# 07_POWER-RAILS.net
KiCad netlist of a schematic drawn in Altium Designer
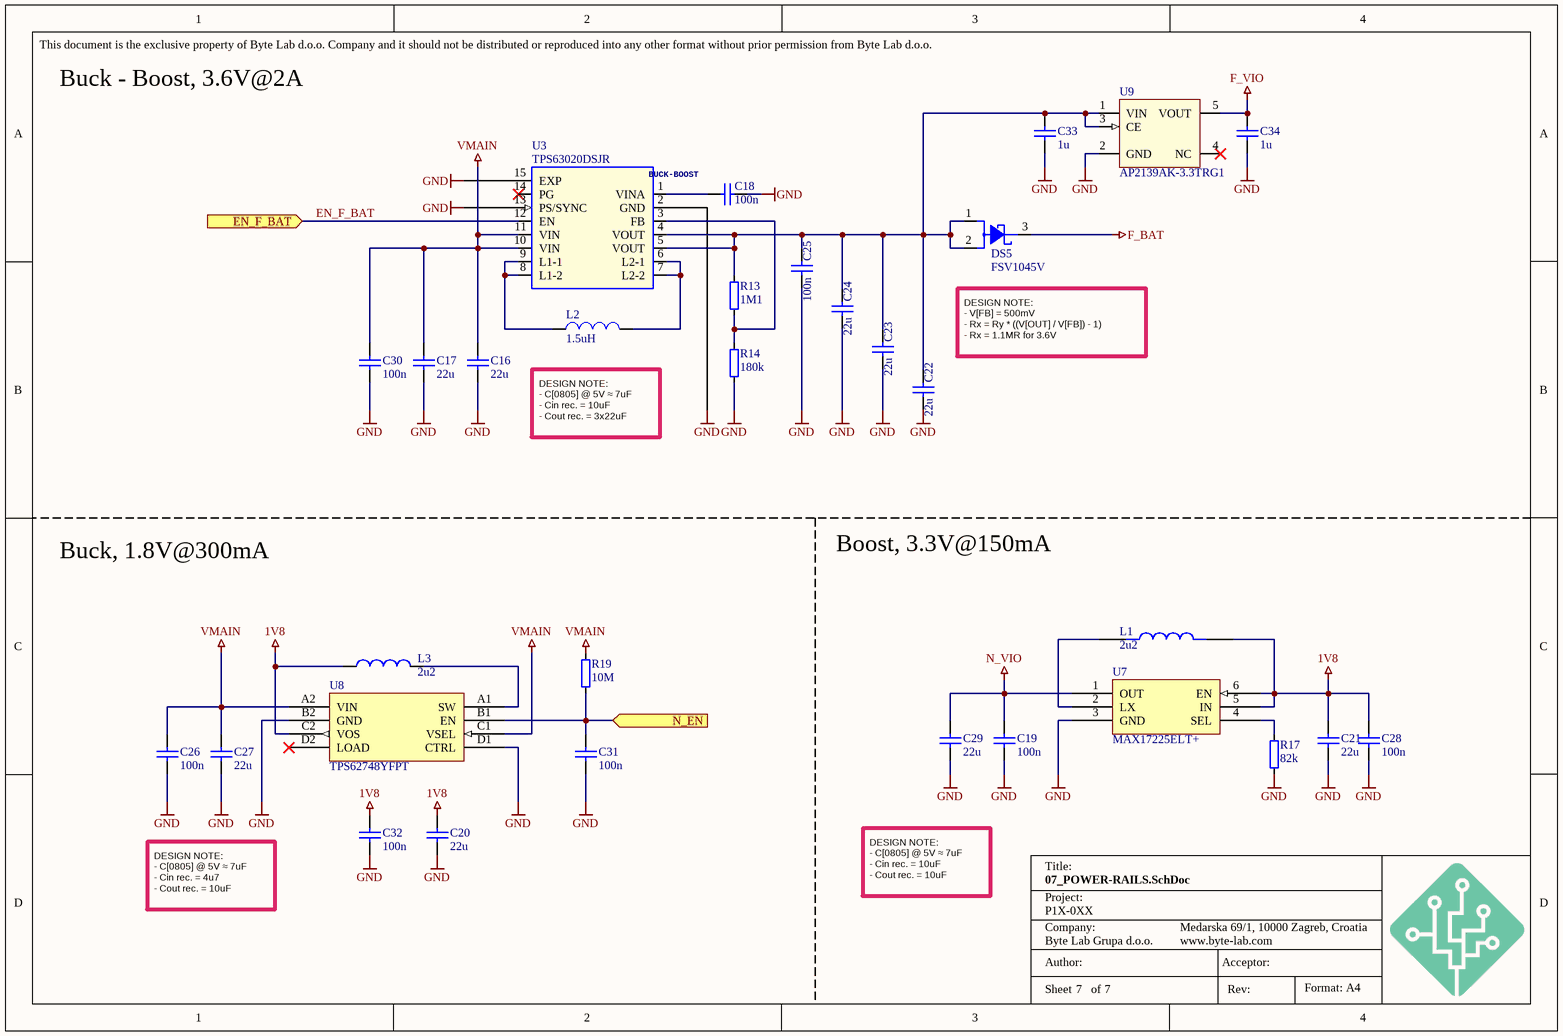
[diagram p0: 07_POWER-RAILS.SchDoc]

(export (version "E")
  (design (tool "Eeschema 10.0.6"))
  (components
    (comp (ref "C16")
      (value "22u")
      (footprint "C-0805")
      (description "Capacitor ceramic 22u ±10% X5R 16V 0805")
      (fields
        (field (name "BL PART NUMBER") "2006-222")
        (field (name "DRAWN_BY") "Fumic")
        (field (name "CHECKED_BY") "Hamin")
      )
      (libsource (lib "BL_Passive") (part "C0805-22u-16V-X5R"))
    )
    (comp (ref "C17")
      (value "22u")
      (footprint "C-0805")
      (description "Capacitor ceramic 22u ±10% X5R 16V 0805")
      (fields
        (field (name "BL PART NUMBER") "2006-222")
        (field (name "DRAWN_BY") "Fumic")
        (field (name "CHECKED_BY") "Hamin")
      )
      (libsource (lib "BL_Passive") (part "C0805-22u-16V-X5R"))
    )
    (comp (ref "C18")
      (value "100n")
      (footprint "C-0402")
      (description "Capacitor ceramic 100n ±10% X7R 16V 0402")
      (fields
        (field (name "BL PART NUMBER") "2000-908")
        (field (name "DRAWN_BY") "Puskar")
        (field (name "CHECKED_BY") "Dodig")
      )
      (libsource (lib "BL_Passive") (part "C0402-100n-16V-X7R"))
    )
    (comp (ref "C19")
      (value "100n")
      (footprint "C-0402")
      (description "Capacitor ceramic 100n ±10% X7R 16V 0402")
      (fields
        (field (name "BL PART NUMBER") "2000-908")
        (field (name "DRAWN_BY") "Puskar")
        (field (name "CHECKED_BY") "Dodig")
      )
      (libsource (lib "BL_Passive") (part "C0402-100n-16V-X7R"))
    )
    (comp (ref "C20")
      (value "22u")
      (footprint "C-0805")
      (description "Capacitor ceramic 22u ±10% X5R 16V 0805")
      (fields
        (field (name "BL PART NUMBER") "2006-222")
        (field (name "DRAWN_BY") "Fumic")
        (field (name "CHECKED_BY") "Hamin")
      )
      (libsource (lib "BL_Passive") (part "C0805-22u-16V-X5R"))
    )
    (comp (ref "C21")
      (value "22u")
      (footprint "C-0805")
      (description "Capacitor ceramic 22u ±10% X5R 16V 0805")
      (fields
        (field (name "BL PART NUMBER") "2006-222")
        (field (name "DRAWN_BY") "Fumic")
        (field (name "CHECKED_BY") "Hamin")
      )
      (libsource (lib "BL_Passive") (part "C0805-22u-16V-X5R"))
    )
    (comp (ref "C22")
      (value "22u")
      (footprint "C-0805")
      (description "Capacitor ceramic 22u ±10% X5R 16V 0805")
      (fields
        (field (name "BL PART NUMBER") "2006-222")
        (field (name "DRAWN_BY") "Fumic")
        (field (name "CHECKED_BY") "Hamin")
      )
      (libsource (lib "BL_Passive") (part "C0805-22u-16V-X5R"))
    )
    (comp (ref "C23")
      (value "22u")
      (footprint "C-0805")
      (description "Capacitor ceramic 22u ±10% X5R 16V 0805")
      (fields
        (field (name "BL PART NUMBER") "2006-222")
        (field (name "DRAWN_BY") "Fumic")
        (field (name "CHECKED_BY") "Hamin")
      )
      (libsource (lib "BL_Passive") (part "C0805-22u-16V-X5R"))
    )
    (comp (ref "C24")
      (value "22u")
      (footprint "C-0805")
      (description "Capacitor ceramic 22u ±10% X5R 16V 0805")
      (fields
        (field (name "BL PART NUMBER") "2006-222")
        (field (name "DRAWN_BY") "Fumic")
        (field (name "CHECKED_BY") "Hamin")
      )
      (libsource (lib "BL_Passive") (part "C0805-22u-16V-X5R"))
    )
    (comp (ref "C25")
      (value "100n")
      (footprint "C-0402")
      (description "Capacitor ceramic 100n ±10% X7R 16V 0402")
      (fields
        (field (name "BL PART NUMBER") "2000-908")
        (field (name "DRAWN_BY") "Puskar")
        (field (name "CHECKED_BY") "Dodig")
      )
      (libsource (lib "BL_Passive") (part "C0402-100n-16V-X7R"))
    )
    (comp (ref "C26")
      (value "100n")
      (footprint "C-0402")
      (description "Capacitor ceramic 100n ±10% X7R 16V 0402")
      (fields
        (field (name "BL PART NUMBER") "2000-908")
        (field (name "DRAWN_BY") "Puskar")
        (field (name "CHECKED_BY") "Dodig")
      )
      (libsource (lib "BL_Passive") (part "C0402-100n-16V-X7R"))
    )
    (comp (ref "C27")
      (value "22u")
      (footprint "C-0805")
      (description "Capacitor ceramic 22u ±10% X5R 16V 0805")
      (fields
        (field (name "BL PART NUMBER") "2006-222")
        (field (name "DRAWN_BY") "Fumic")
        (field (name "CHECKED_BY") "Hamin")
      )
      (libsource (lib "BL_Passive") (part "C0805-22u-16V-X5R"))
    )
    (comp (ref "C28")
      (value "100n")
      (footprint "C-0402")
      (description "Capacitor ceramic 100n ±10% X7R 16V 0402")
      (fields
        (field (name "BL PART NUMBER") "2000-908")
        (field (name "DRAWN_BY") "Puskar")
        (field (name "CHECKED_BY") "Dodig")
      )
      (libsource (lib "BL_Passive") (part "C0402-100n-16V-X7R"))
    )
    (comp (ref "C29")
      (value "22u")
      (footprint "C-0805")
      (description "Capacitor ceramic 22u ±10% X5R 16V 0805")
      (fields
        (field (name "BL PART NUMBER") "2006-222")
        (field (name "DRAWN_BY") "Fumic")
        (field (name "CHECKED_BY") "Hamin")
      )
      (libsource (lib "BL_Passive") (part "C0805-22u-16V-X5R"))
    )
    (comp (ref "C30")
      (value "100n")
      (footprint "C-0402")
      (description "Capacitor ceramic 100n ±10% X7R 16V 0402")
      (fields
        (field (name "BL PART NUMBER") "2000-908")
        (field (name "DRAWN_BY") "Puskar")
        (field (name "CHECKED_BY") "Dodig")
      )
      (libsource (lib "BL_Passive") (part "C0402-100n-16V-X7R"))
    )
    (comp (ref "C31")
      (value "100n")
      (footprint "C-0402")
      (description "Capacitor ceramic 100n ±10% X7R 16V 0402")
      (fields
        (field (name "BL PART NUMBER") "2000-908")
        (field (name "DRAWN_BY") "Puskar")
        (field (name "CHECKED_BY") "Dodig")
      )
      (libsource (lib "BL_Passive") (part "C0402-100n-16V-X7R"))
    )
    (comp (ref "C32")
      (value "100n")
      (footprint "C-0402")
      (description "Capacitor ceramic 100n ±10% X7R 16V 0402")
      (fields
        (field (name "BL PART NUMBER") "2000-908")
        (field (name "DRAWN_BY") "Puskar")
        (field (name "CHECKED_BY") "Dodig")
      )
      (libsource (lib "BL_Passive") (part "C0402-100n-16V-X7R"))
    )
    (comp (ref "C33")
      (value "1u")
      (footprint "C-0603")
      (description "Capacitor ceramic 1u ±10% X5R 25V")
      (fields
        (field (name "MANUFACTURER") "Yageo")
        (field (name "BL PART NUMBER") "2006-223")
        (field (name "DRAWN_BY") "Hamin")
        (field (name "CHECKED_BY") "Golubic")
      )
      (libsource (lib "BL_Passive") (part "C0603-1u-25V-X5R"))
    )
    (comp (ref "C34")
      (value "1u")
      (footprint "C-0603")
      (description "Capacitor ceramic 1u ±10% X5R 25V")
      (fields
        (field (name "MANUFACTURER") "Yageo")
        (field (name "BL PART NUMBER") "2006-223")
        (field (name "DRAWN_BY") "Hamin")
        (field (name "CHECKED_BY") "Golubic")
      )
      (libsource (lib "BL_Passive") (part "C0603-1u-25V-X5R"))
    )
    (comp (ref "DS5")
      (value "FSV1045V")
      (footprint "TO277-3")
      (description "DIODO SCHOTTKY 10A 45V FSV1045V TO277-3 SMT")
      (fields
        (field (name "BL PART NUMBER") "2007-712")
        (field (name "MANUFACTURER") "onsemi")
        (field (name "DRAWN_BY") "Blues Wireless")
      )
      (libsource (lib "n21-p2") (part "SCHOTTKY - FSV1045V - 10A/45V"))
    )
    (comp (ref "L1")
      (value "2u2")
      (footprint "IND_XFL4020-222MEC")
      (description "Power Inductors - SMD 2.2Uh Shld 8A 23.5mOhms AECQ2")
      (fields (field (name "BL PART NUMBER") "2007-483") (field (name "DRAWN_BY") "Blues Wireless"))
      (libsource (lib "n21-p2") (part "XFL4020-222MEC"))
    )
    (comp (ref "L2")
      (value "1.5uH")
      (footprint "VCHA042A-1R5MS6")
      (description "Fixed Ind 1.5UH 7.3A 15.4 Mohm")
      (fields
        (field (name "MANUFACTURER") "Cyntec")
        (field (name "MANUFACTURER PART NUMBER") "VCHA042A-1R5MS6")
        (field (name "DRAWN_BY") "Blues Wireless")
      )
      (libsource (lib "n21-p2") (part "VCHA042A-1R5MS6"))
    )
    (comp (ref "L3")
      (value "2u2")
      (footprint "1285AS-H-2R2M=P2-INDC2016X100N")
      (description "FIXED IND 2.2UH 1.5A 204MOHM SMD")
      (fields
        (field (name "MANUFACTURER") "Murata Electronics")
        (field (name "MANUFACTURER PART NUMBER") "1285AS-H-2R2M=P2")
        (field (name "DRAWN_BY") "Blues Wireless")
      )
      (libsource (lib "n21-p2") (part "1285AS-H-2R2M=P2"))
    )
    (comp (ref "R13")
      (value "1M1")
      (footprint "R-0402")
      (description "Resistor 1M1 ±1% 0402")
      (fields
        (field (name "BL PART NUMBER") "2000-730")
        (field (name "CHECKED_BY") "Kvesic")
        (field (name "DRAWN_BY") "Hamin")
      )
      (libsource (lib "BL_Passive") (part "R0402-1M1-1"))
    )
    (comp (ref "R14")
      (value "180k")
      (footprint "R-0402")
      (description "Resistor 180k ±1% 0402")
      (fields
        (field (name "BL PART NUMBER") "2001-422")
        (field (name "CHECKED_BY") "Hamin")
        (field (name "DRAWN_BY") "Dodig")
      )
      (libsource (lib "BL_Passive") (part "R0402-180k-1"))
    )
    (comp (ref "R17")
      (value "82k")
      (footprint "R-0402")
      (description "Resistor 82k ±1% 0402")
      (fields
        (field (name "MANUFACTURER") "Yageo")
        (field (name "MANUFACTURER PART NUMBER") "RC0402FR-0782KL")
        (field (name "CHECKED_BY") "Hamin")
        (field (name "DRAWN_BY") "Puskar")
      )
      (libsource (lib "BL_Passive") (part "R0402-82k-1"))
    )
    (comp (ref "R19")
      (value "10M")
      (footprint "BL_Passive:R-0402")
      (description "Resistor 10M ±1% 0402")
      (fields
        (field (name "BL PART NUMBER") "2002-832")
        (field (name "CHECKED_BY") "Dodig")
        (field (name "DRAWN_BY") "Zvonc")
      )
      (libsource (lib "BL_Passive") (part "R0402-10M-1"))
    )
    (comp (ref "U3")
      (value "TPS63020DSJR")
      (footprint "TI PVSON-14 DSJ")
      (description "I.C. DC/DC CONVERTER TPS63020DSJR TEXAS VSON14 SMT")
      (fields
        (field (name "BL PART NUMBER") "2002-405")
        (field (name "MANUFACTURER") "Texas Instruments")
        (field (name "DRAWN_BY") "Blues Wireless")
      )
      (libsource (lib "n21-p2") (part "BUCK-BOOST - TPS63020DSJR"))
    )
    (comp (ref "U7")
      (value "MAX17225ELT+")
      (footprint "MAX17225ELT+UDFN")
      (description "IC REG BOOST ADJ 1A NANO 6UDFN")
      (fields
        (field (name "MANUFACTURER") "Maxim")
        (field (name "BL PART NUMBER") "2007-481")
        (field (name "DRAWN_BY") "Blues Wireless")
      )
      (libsource (lib "n21-p2") (part "MAX17225ELT+"))
    )
    (comp (ref "U8")
      (value "TPS62748YFPT")
      (footprint "TPS62748YFPT-DSBGA4x2")
      (description "IC REG BUCK PROG 300MA 8DSBGA")
      (fields
        (field (name "MANUFACTURER") "Texas Instruments")
        (field (name "BL PART NUMBER") "2007-480")
        (field (name "DRAWN_BY") "Blues Wireless")
      )
      (libsource (lib "n21-p2") (part "TPS62748YFPT"))
    )
    (comp (ref "U9")
      (value "AP2139AK-3.3TRG1")
      (footprint "BL_Components:SOT-23-5(M5)")
      (description "IC REG LINEAR 3.3V 250MA SOT23-5")
      (fields
        (field (name "MANUFACTURER") "Diodes Incorporated")
        (field (name "BL PART NUMBER") "2006-845")
        (field (name "CHECKED_BY") "Hlupic")
        (field (name "DRAWN_BY") "Marsic")
      )
      (libsource (lib "BL_Analog") (part "AP2139AK-3.3TRG1"))
    )
  )
  (nets
    (net (code "1") (name "/EN_F_BAT") (class "Default")
      (node (ref "U3") (pin "12") (pinfunction "EN_12") (pintype "passive"))
    )
    (net (code "2") (name "/N_EN") (class "Default")
      (node (ref "C31") (pin "2") (pinfunction "2_2") (pintype "passive"))
      (node (ref "R19") (pin "1") (pintype "passive"))
      (node (ref "U8") (pin "B1") (pinfunction "EN_B1") (pintype "passive"))
    )
    (net (code "3") (name "1V8") (class "Default")
      (node (ref "C20") (pin "1") (pinfunction "1_1") (pintype "passive"))
      (node (ref "C21") (pin "2") (pinfunction "2_2") (pintype "passive"))
      (node (ref "C28") (pin "2") (pinfunction "2_2") (pintype "passive"))
      (node (ref "C32") (pin "2") (pinfunction "2_2") (pintype "passive"))
      (node (ref "L1") (pin "2") (pinfunction "2_2") (pintype "passive"))
      (node (ref "L3") (pin "1") (pinfunction "1_1") (pintype "passive"))
      (node (ref "U7") (pin "5") (pinfunction "IN_5") (pintype "passive"))
      (node (ref "U7") (pin "6") (pinfunction "EN_6") (pintype "input"))
      (node (ref "U8") (pin "C2") (pinfunction "VOS_C2") (pintype "output"))
    )
    (net (code "4") (name "F_BAT") (class "Default")
      (node (ref "DS5") (pin "3") (pinfunction "C_3") (pintype "passive"))
    )
    (net (code "5") (name "F_VIO") (class "Default")
      (node (ref "C34") (pin "2") (pinfunction "2_2") (pintype "passive"))
      (node (ref "U9") (pin "5") (pinfunction "VOUT_5") (pintype "power_in"))
    )
    (net (code "6") (name "GND") (class "Default")
      (node (ref "C16") (pin "1") (pinfunction "1_1") (pintype "passive"))
      (node (ref "C17") (pin "1") (pinfunction "1_1") (pintype "passive"))
      (node (ref "C18") (pin "1") (pinfunction "1_1") (pintype "passive"))
      (node (ref "C19") (pin "1") (pinfunction "1_1") (pintype "passive"))
      (node (ref "C20") (pin "2") (pinfunction "2_2") (pintype "passive"))
      (node (ref "C21") (pin "1") (pinfunction "1_1") (pintype "passive"))
      (node (ref "C22") (pin "2") (pinfunction "2_2") (pintype "passive"))
      (node (ref "C23") (pin "2") (pinfunction "2_2") (pintype "passive"))
      (node (ref "C24") (pin "2") (pinfunction "2_2") (pintype "passive"))
      (node (ref "C25") (pin "1") (pinfunction "1_1") (pintype "passive"))
      (node (ref "C26") (pin "1") (pinfunction "1_1") (pintype "passive"))
      (node (ref "C27") (pin "1") (pinfunction "1_1") (pintype "passive"))
      (node (ref "C28") (pin "1") (pinfunction "1_1") (pintype "passive"))
      (node (ref "C29") (pin "2") (pinfunction "2_2") (pintype "passive"))
      (node (ref "C30") (pin "1") (pinfunction "1_1") (pintype "passive"))
      (node (ref "C31") (pin "1") (pinfunction "1_1") (pintype "passive"))
      (node (ref "C32") (pin "1") (pinfunction "1_1") (pintype "passive"))
      (node (ref "C33") (pin "1") (pinfunction "1_1") (pintype "passive"))
      (node (ref "C34") (pin "1") (pinfunction "1_1") (pintype "passive"))
      (node (ref "R14") (pin "1") (pintype "passive"))
      (node (ref "R17") (pin "2") (pintype "passive"))
      (node (ref "U3") (pin "13") (pinfunction "PS/SYNC_13") (pintype "input"))
      (node (ref "U3") (pin "15") (pinfunction "EXP_15") (pintype "passive"))
      (node (ref "U3") (pin "2") (pinfunction "GND_2") (pintype "power_in"))
      (node (ref "U7") (pin "3") (pinfunction "GND_3") (pintype "passive"))
      (node (ref "U8") (pin "B2") (pinfunction "GND_B2") (pintype "passive"))
      (node (ref "U8") (pin "D1") (pinfunction "CTRL_D1") (pintype "passive"))
      (node (ref "U9") (pin "2") (pinfunction "GND_2") (pintype "power_in"))
    )
    (net (code "7") (name "N_VIO") (class "Default")
      (node (ref "C19") (pin "2") (pinfunction "2_2") (pintype "passive"))
      (node (ref "C29") (pin "1") (pinfunction "1_1") (pintype "passive"))
      (node (ref "U7") (pin "1") (pinfunction "OUT_1") (pintype "passive"))
    )
    (net (code "8") (name "Net-(DS5-A1)") (class "Default")
      (node (ref "C22") (pin "1") (pinfunction "1_1") (pintype "passive"))
      (node (ref "C23") (pin "1") (pinfunction "1_1") (pintype "passive"))
      (node (ref "C24") (pin "1") (pinfunction "1_1") (pintype "passive"))
      (node (ref "C25") (pin "2") (pinfunction "2_2") (pintype "passive"))
      (node (ref "C33") (pin "2") (pinfunction "2_2") (pintype "passive"))
      (node (ref "DS5") (pin "1") (pinfunction "A1_1") (pintype "passive"))
      (node (ref "DS5") (pin "2") (pinfunction "A2_2") (pintype "passive"))
      (node (ref "R13") (pin "2") (pintype "passive"))
      (node (ref "U3") (pin "4") (pinfunction "VOUT_4") (pintype "power_in"))
      (node (ref "U3") (pin "5") (pinfunction "VOUT_5") (pintype "power_in"))
      (node (ref "U9") (pin "1") (pinfunction "VIN_1") (pintype "power_in"))
      (node (ref "U9") (pin "3") (pinfunction "CE_3") (pintype "input"))
    )
    (net (code "9") (name "Net-(L2-A)") (class "Default")
      (node (ref "L2") (pin "2") (pinfunction "A_2") (pintype "passive"))
      (node (ref "U3") (pin "8") (pinfunction "L1-2_8") (pintype "passive"))
      (node (ref "U3") (pin "9") (pinfunction "L1-1_9") (pintype "passive"))
    )
    (net (code "10") (name "Net-(L2-C)") (class "Default")
      (node (ref "L2") (pin "1") (pinfunction "C_1") (pintype "passive"))
      (node (ref "U3") (pin "6") (pinfunction "L2-1_6") (pintype "passive"))
      (node (ref "U3") (pin "7") (pinfunction "L2-2_7") (pintype "passive"))
    )
    (net (code "11") (name "Net-(U3-FB)") (class "Default")
      (node (ref "R13") (pin "1") (pintype "passive"))
      (node (ref "R14") (pin "2") (pintype "passive"))
      (node (ref "U3") (pin "3") (pinfunction "FB_3") (pintype "passive"))
    )
    (net (code "12") (name "Net-(U3-VINA)") (class "Default")
      (node (ref "C18") (pin "2") (pinfunction "2_2") (pintype "passive"))
      (node (ref "U3") (pin "1") (pinfunction "VINA_1") (pintype "power_in"))
    )
    (net (code "13") (name "Net-(U7-LX)") (class "Default")
      (node (ref "L1") (pin "1") (pinfunction "1_1") (pintype "passive"))
      (node (ref "U7") (pin "2") (pinfunction "LX_2") (pintype "passive"))
    )
    (net (code "14") (name "Net-(U7-SEL)") (class "Default")
      (node (ref "R17") (pin "1") (pintype "passive"))
      (node (ref "U7") (pin "4") (pinfunction "SEL_4") (pintype "passive"))
    )
    (net (code "15") (name "Net-(U8-SW)") (class "Default")
      (node (ref "L3") (pin "2") (pinfunction "2_2") (pintype "passive"))
      (node (ref "U8") (pin "A1") (pinfunction "SW_A1") (pintype "passive"))
    )
    (net (code "16") (name "VMAIN") (class "Default")
      (node (ref "C16") (pin "2") (pinfunction "2_2") (pintype "passive"))
      (node (ref "C17") (pin "2") (pinfunction "2_2") (pintype "passive"))
      (node (ref "C26") (pin "2") (pinfunction "2_2") (pintype "passive"))
      (node (ref "C27") (pin "2") (pinfunction "2_2") (pintype "passive"))
      (node (ref "C30") (pin "2") (pinfunction "2_2") (pintype "passive"))
      (node (ref "R19") (pin "2") (pintype "passive"))
      (node (ref "U3") (pin "10") (pinfunction "VIN_10") (pintype "power_in"))
      (node (ref "U3") (pin "11") (pinfunction "VIN_11") (pintype "power_in"))
      (node (ref "U8") (pin "A2") (pinfunction "VIN_A2") (pintype "passive"))
      (node (ref "U8") (pin "C1") (pinfunction "VSEL_C1") (pintype "input"))
    )
    (net (code "17") (name "unconnected-(U3-PG-Pad14)") (class "Default")
      (node (ref "U3") (pin "14") (pinfunction "PG_14") (pintype "open_collector+no_connect"))
    )
    (net (code "18") (name "unconnected-(U8-LOAD-PadD2)") (class "Default")
      (node (ref "U8") (pin "D2") (pinfunction "LOAD_D2") (pintype "passive+no_connect"))
    )
    (net (code "19") (name "unconnected-(U9-NC-Pad4)") (class "Default")
      (node (ref "U9") (pin "4") (pinfunction "NC_4") (pintype "passive+no_connect"))
    )
  )
)
